# reduktor_net.net
KiCad netlist of a schematic drawn in EAGLE
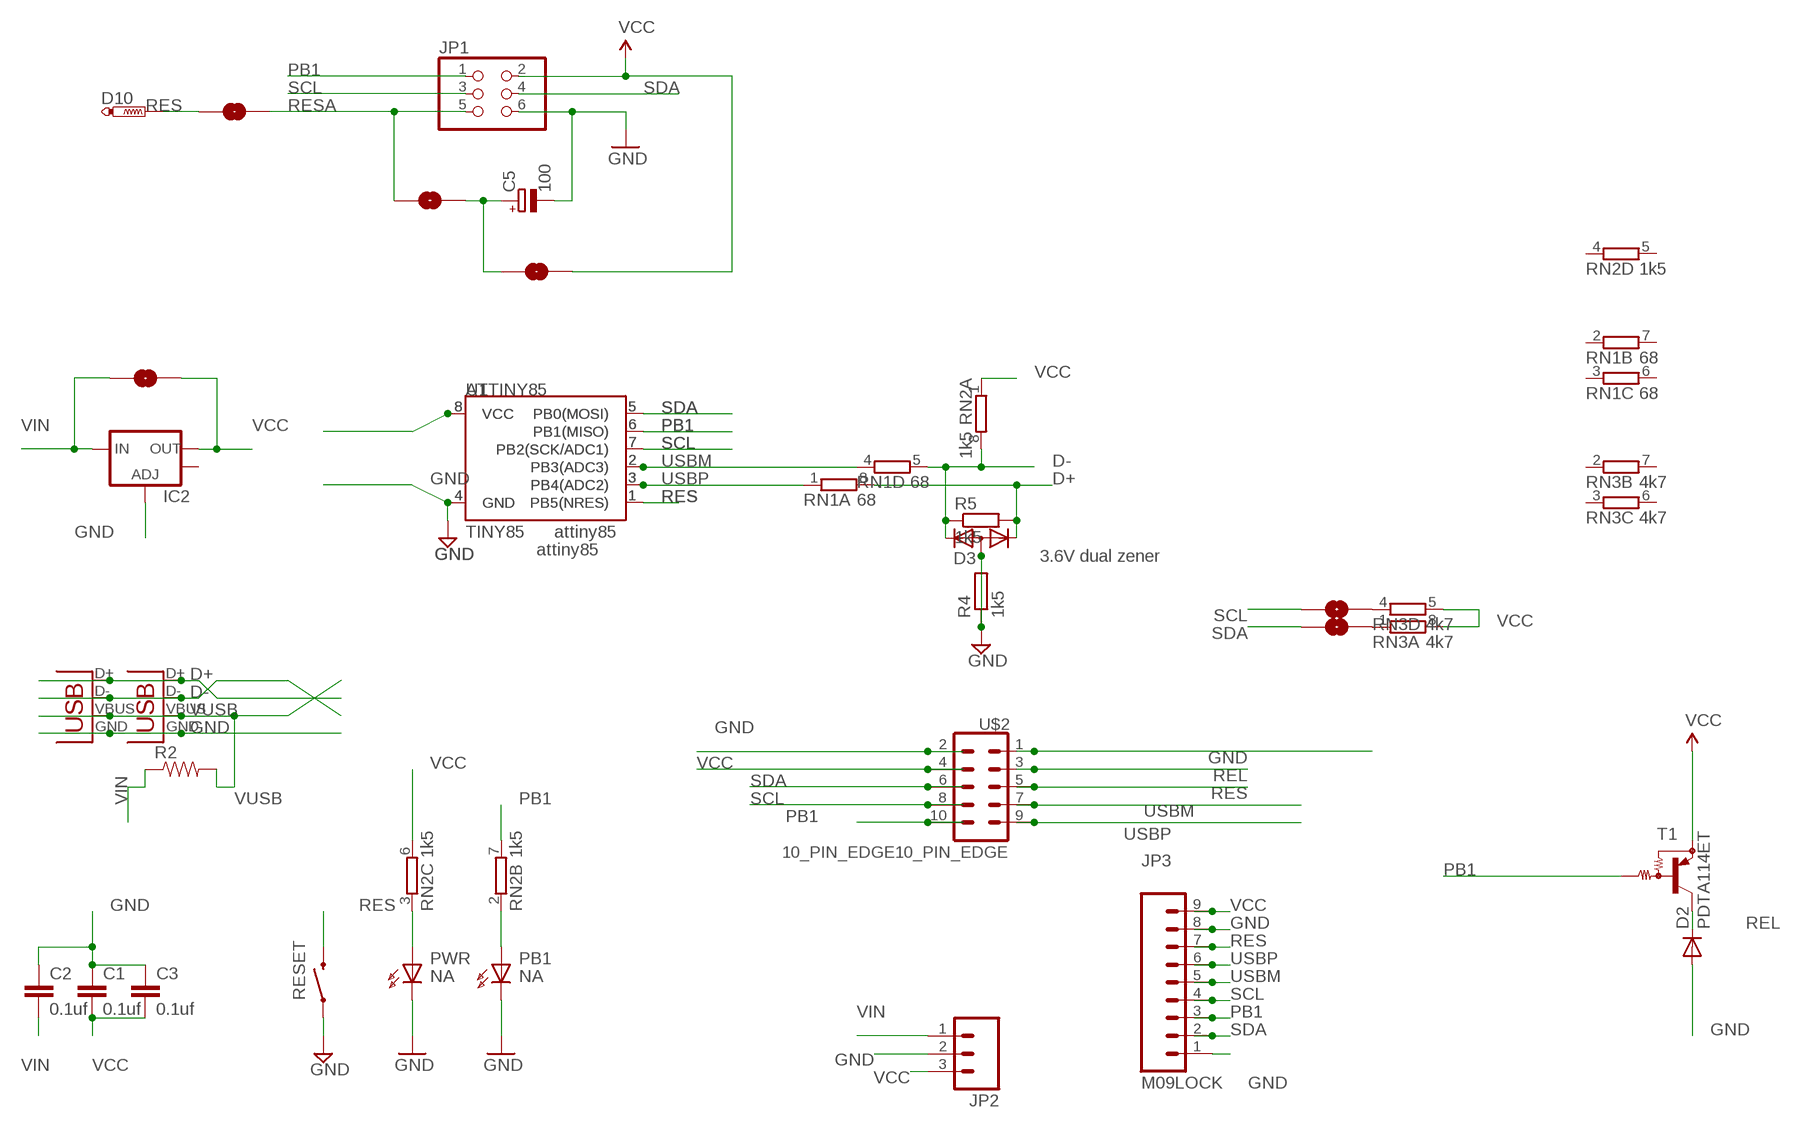
[diagram p0: schematic, sheet 1]

(export (version "E")
  (design (tool "Eeschema 10.0.6"))
  (components
    (comp (ref "ATTINY85")
      (value "ATTINY45")
      (footprint "eagle-import:SO08-EIAJ")
      (libsource (lib "eagle-import") (part "ATTINY45"))
    )
    (comp (ref "C1")
      (value "0.1uf")
      (footprint "eagle-import:0603-CAP")
      (libsource (lib "eagle-import") (part "CAP0603-CAP"))
    )
    (comp (ref "C2")
      (value "0.1uf")
      (footprint "eagle-import:0603-CAP")
      (libsource (lib "eagle-import") (part "CAP0603-CAP"))
    )
    (comp (ref "C3")
      (value "0.1uf")
      (footprint "eagle-import:0603-CAP")
      (libsource (lib "eagle-import") (part "CAP0603-CAP"))
    )
    (comp (ref "C5")
      (value "100")
      (footprint "eagle-import:153CLV-0405")
      (libsource (lib "eagle-import") (part "CPOL-EU153CLV-0405"))
    )
    (comp (ref "D2")
      (value "DIODESOD")
      (footprint "eagle-import:SOD-323")
      (libsource (lib "eagle-import") (part "DIODESOD"))
    )
    (comp (ref "D3")
      (value "3.6V dual zener")
      (footprint "eagle-import:SOT23")
      (libsource (lib "eagle-import") (part "DIODE-2CA|ACSOT23"))
    )
    (comp (ref "D10")
      (value "PTR1TP14SQ")
      (footprint "eagle-import:TP14SQ")
      (libsource (lib "eagle-import") (part "PTR1TP14SQ"))
    )
    (comp (ref "FUSE1")
      (value "SOLDERJUMPERNO")
      (footprint "eagle-import:SJ_2S-NO")
      (libsource (lib "eagle-import") (part "SOLDERJUMPERNO"))
    )
    (comp (ref "FUSE2")
      (value "SOLDERJUMPERNO")
      (footprint "eagle-import:SJ_2S-NO")
      (libsource (lib "eagle-import") (part "SOLDERJUMPERNO"))
    )
    (comp (ref "FUSE3")
      (value "SOLDERJUMPERNO")
      (footprint "eagle-import:SJ_2S-NO")
      (libsource (lib "eagle-import") (part "SOLDERJUMPERNO"))
    )
    (comp (ref "FUSE4")
      (value "SOLDERJUMPERNO")
      (footprint "eagle-import:SJ_2S-NO")
      (libsource (lib "eagle-import") (part "SOLDERJUMPERNO"))
    )
    (comp (ref "FUSE5")
      (value "SOLDERJUMPERNO")
      (footprint "eagle-import:SJ_2S-NO")
      (libsource (lib "eagle-import") (part "SOLDERJUMPERNO"))
    )
    (comp (ref "FUSE6")
      (value "SOLDERJUMPERNO")
      (footprint "eagle-import:SJ_2S-NO")
      (libsource (lib "eagle-import") (part "SOLDERJUMPERNO"))
    )
    (comp (ref "IC2")
      (value "V_REG_LM1117SOT223")
      (footprint "eagle-import:SOT223")
      (libsource (lib "eagle-import") (part "V_REG_LM1117SOT223"))
    )
    (comp (ref "JP1")
      (value "PINHD-2X3")
      (footprint "eagle-import:2X03")
      (libsource (lib "eagle-import") (part "PINHD-2X3"))
    )
    (comp (ref "JP2")
      (value "M03LOCK")
      (footprint "eagle-import:1X03_LOCK")
      (libsource (lib "eagle-import") (part "M03LOCK"))
    )
    (comp (ref "JP3")
      (value "M09LOCK")
      (footprint "eagle-import:1X09_LOCK")
      (libsource (lib "eagle-import") (part "M09LOCK"))
    )
    (comp (ref "PB1")
      (value "NA")
      (footprint "eagle-import:LED-0603")
      (libsource (lib "eagle-import") (part "LED0603DWS"))
    )
    (comp (ref "PWR")
      (value "NA")
      (footprint "eagle-import:LED-0603")
      (libsource (lib "eagle-import") (part "LED0603DWS"))
    )
    (comp (ref "R2")
      (value "RESISTOR0603-RES")
      (footprint "eagle-import:0603-RES")
      (libsource (lib "eagle-import") (part "RESISTOR0603-RES"))
    )
    (comp (ref "R4")
      (value "1k5")
      (footprint "eagle-import:R0603")
      (libsource (lib "eagle-import") (part "R-EU_R0603"))
    )
    (comp (ref "R5")
      (value "1k5")
      (footprint "eagle-import:R0603")
      (libsource (lib "eagle-import") (part "R-EU_R0603"))
    )
    (comp (ref "RESET")
      (value "SWITCH-MOMENTARY-2-SMD-1101NE")
      (footprint "eagle-import:TACTILE-SWITCH-1101NE")
      (libsource (lib "eagle-import") (part "SWITCH-MOMENTARY-2-SMD-1101NE"))
    )
    (comp (ref "RN1")
      (value "68")
      (footprint "eagle-import:0603-ARC")
      (libsource (lib "eagle-import") (part "4R-N0603-ARC"))
    )
    (comp (ref "RN2")
      (value "1k5")
      (footprint "eagle-import:0603-ARC")
      (libsource (lib "eagle-import") (part "4R-N0603-ARC"))
    )
    (comp (ref "RN3")
      (value "4k7")
      (footprint "eagle-import:0603-ARC")
      (fields (field (name "OC_FARNELL") "unknown") (field (name "OC_NEWARK") "unknown"))
      (libsource (lib "eagle-import") (part "4R-N0603-ARC"))
    )
    (comp (ref "T1")
      (value "PDTA114ET")
      (footprint "eagle-import:ES_SOT23-3")
      (libsource (lib "eagle-import") (part "ES_PNP-DRIVERSOT23-3"))
    )
    (comp (ref "U$2")
      (value "10_PIN_EDGE10_PIN_EDGE")
      (footprint "eagle-import:10_PIN_EDGE")
      (libsource (lib "eagle-import") (part "10_PIN_EDGE10_PIN_EDGE"))
    )
    (comp (ref "U1")
      (value "TINY85")
      (footprint "eagle-import:DIP08")
      (libsource (lib "eagle-import") (part "ATTINY45TINY45-20-DIP"))
    )
    (comp (ref "X5")
      (value "USBSMD")
      (footprint "eagle-import:USB-MINIB")
      (libsource (lib "eagle-import") (part "USBSMD"))
    )
    (comp (ref "X6")
      (value "USB-MICROB")
      (footprint "eagle-import:USB-MICROB")
      (libsource (lib "eagle-import") (part "USB-MICROB"))
    )
  )
  (nets
    (net (code "1") (name "/D+") (class "Default")
      (node (ref "D3") (pin "1") (pinfunction "K1_1") (pintype "passive"))
      (node (ref "R5") (pin "2") (pinfunction "2_2") (pintype "passive"))
      (node (ref "RN1") (pin "8") (pinfunction "2_8") (pintype "passive"))
      (node (ref "X5") (pin "D+") (pinfunction "D+_D+") (pintype "bidirectional"))
      (node (ref "X6") (pin "D+") (pinfunction "D+_D+") (pintype "bidirectional"))
    )
    (net (code "2") (name "/D-") (class "Default")
      (node (ref "D3") (pin "2") (pinfunction "K2_2") (pintype "passive"))
      (node (ref "R5") (pin "1") (pinfunction "1_1") (pintype "passive"))
      (node (ref "RN1") (pin "5") (pinfunction "2_5") (pintype "passive"))
      (node (ref "RN2") (pin "8") (pinfunction "2_8") (pintype "passive"))
      (node (ref "X5") (pin "D-") (pinfunction "D-_D-") (pintype "bidirectional"))
      (node (ref "X6") (pin "D-") (pinfunction "D-_D-") (pintype "bidirectional"))
    )
    (net (code "3") (name "/PB1") (class "Default")
      (node (ref "ATTINY85") (pin "6") (pinfunction "PB1(MISO)_6") (pintype "bidirectional"))
      (node (ref "JP1") (pin "1") (pinfunction "1_1") (pintype "passive"))
      (node (ref "JP3") (pin "3") (pinfunction "3_3") (pintype "passive"))
      (node (ref "RN2") (pin "7") (pinfunction "2_7") (pintype "passive"))
      (node (ref "T1") (pin "1") (pinfunction "B_1") (pintype "passive"))
      (node (ref "U$2") (pin "10") (pinfunction "10_10") (pintype "passive"))
      (node (ref "U1") (pin "6") (pinfunction "PB1(MISO)_6") (pintype "bidirectional"))
    )
    (net (code "4") (name "/REL") (class "Default")
      (node (ref "D2") (pin "1") (pinfunction "C_1") (pintype "passive"))
      (node (ref "T1") (pin "3") (pinfunction "C_3") (pintype "passive"))
      (node (ref "U$2") (pin "3") (pinfunction "3_3") (pintype "passive"))
    )
    (net (code "5") (name "/RES") (class "Default")
      (node (ref "ATTINY85") (pin "1") (pinfunction "PB5(NRES)_1") (pintype "bidirectional"))
      (node (ref "D10") (pin "TP") (pinfunction "TP_TP") (pintype "input"))
      (node (ref "FUSE1") (pin "1") (pinfunction "1_1") (pintype "passive"))
      (node (ref "JP3") (pin "7") (pinfunction "7_7") (pintype "passive"))
      (node (ref "RESET") (pin "P$2") (pinfunction "2_P$2") (pintype "passive"))
      (node (ref "U$2") (pin "5") (pinfunction "5_5") (pintype "passive"))
      (node (ref "U1") (pin "1") (pinfunction "PB5(NRES)_1") (pintype "bidirectional"))
    )
    (net (code "6") (name "/RESA") (class "Default")
      (node (ref "FUSE1") (pin "2") (pinfunction "2_2") (pintype "passive"))
      (node (ref "FUSE3") (pin "1") (pinfunction "1_1") (pintype "passive"))
      (node (ref "JP1") (pin "5") (pinfunction "5_5") (pintype "passive"))
    )
    (net (code "7") (name "/SCL") (class "Default")
      (node (ref "ATTINY85") (pin "7") (pinfunction "PB2(SCK/ADC1)_7") (pintype "bidirectional"))
      (node (ref "FUSE4") (pin "1") (pinfunction "1_1") (pintype "passive"))
      (node (ref "JP1") (pin "3") (pinfunction "3_3") (pintype "passive"))
      (node (ref "JP3") (pin "4") (pinfunction "4_4") (pintype "passive"))
      (node (ref "U$2") (pin "8") (pinfunction "8_8") (pintype "passive"))
      (node (ref "U1") (pin "7") (pinfunction "PB2(SCK/ADC1)_7") (pintype "bidirectional"))
    )
    (net (code "8") (name "/SDA") (class "Default")
      (node (ref "ATTINY85") (pin "5") (pinfunction "PB0(MOSI)_5") (pintype "bidirectional"))
      (node (ref "FUSE5") (pin "1") (pinfunction "1_1") (pintype "passive"))
      (node (ref "JP1") (pin "4") (pinfunction "4_4") (pintype "passive"))
      (node (ref "JP3") (pin "2") (pinfunction "2_2") (pintype "passive"))
      (node (ref "U$2") (pin "6") (pinfunction "6_6") (pintype "passive"))
      (node (ref "U1") (pin "5") (pinfunction "PB0(MOSI)_5") (pintype "bidirectional"))
    )
    (net (code "9") (name "/USBM") (class "Default")
      (node (ref "ATTINY85") (pin "2") (pinfunction "PB3(ADC3)_2") (pintype "bidirectional"))
      (node (ref "JP3") (pin "5") (pinfunction "5_5") (pintype "passive"))
      (node (ref "RN1") (pin "4") (pinfunction "1_4") (pintype "passive"))
      (node (ref "U$2") (pin "7") (pinfunction "7_7") (pintype "passive"))
      (node (ref "U1") (pin "2") (pinfunction "PB3(ADC3)_2") (pintype "bidirectional"))
    )
    (net (code "10") (name "/USBP") (class "Default")
      (node (ref "ATTINY85") (pin "3") (pinfunction "PB4(ADC2)_3") (pintype "bidirectional"))
      (node (ref "JP3") (pin "6") (pinfunction "6_6") (pintype "passive"))
      (node (ref "RN1") (pin "1") (pinfunction "1_1") (pintype "passive"))
      (node (ref "U$2") (pin "9") (pinfunction "9_9") (pintype "passive"))
      (node (ref "U1") (pin "3") (pinfunction "PB4(ADC2)_3") (pintype "bidirectional"))
    )
    (net (code "11") (name "/VIN") (class "Default")
      (node (ref "C2") (pin "2") (pinfunction "2_2") (pintype "passive"))
      (node (ref "FUSE2") (pin "1") (pinfunction "1_1") (pintype "passive"))
      (node (ref "IC2") (pin "3") (pinfunction "IN_3") (pintype "input"))
      (node (ref "JP2") (pin "1") (pinfunction "1_1") (pintype "passive"))
      (node (ref "R2") (pin "1") (pinfunction "1_1") (pintype "passive"))
    )
    (net (code "12") (name "/VUSB") (class "Default")
      (node (ref "R2") (pin "2") (pinfunction "2_2") (pintype "passive"))
      (node (ref "X5") (pin "VBUS") (pinfunction "VBUS_VBUS") (pintype "bidirectional"))
      (node (ref "X6") (pin "VBUS") (pinfunction "VBUS_VBUS") (pintype "bidirectional"))
    )
    (net (code "13") (name "GND") (class "Default")
      (node (ref "ATTINY85") (pin "4") (pinfunction "GND_4") (pintype "bidirectional"))
      (node (ref "C1") (pin "1") (pinfunction "1_1") (pintype "passive"))
      (node (ref "C2") (pin "1") (pinfunction "1_1") (pintype "passive"))
      (node (ref "C3") (pin "1") (pinfunction "1_1") (pintype "passive"))
      (node (ref "C5") (pin "-") (pinfunction "-_-") (pintype "passive"))
      (node (ref "D2") (pin "2") (pinfunction "A_2") (pintype "passive"))
      (node (ref "D3") (pin "3") (pinfunction "A_3") (pintype "passive"))
      (node (ref "IC2") (pin "1") (pinfunction "ADJ_1") (pintype "input"))
      (node (ref "JP1") (pin "6") (pinfunction "6_6") (pintype "passive"))
      (node (ref "JP2") (pin "2") (pinfunction "2_2") (pintype "passive"))
      (node (ref "JP3") (pin "1") (pinfunction "1_1") (pintype "passive"))
      (node (ref "JP3") (pin "8") (pinfunction "8_8") (pintype "passive"))
      (node (ref "PB1") (pin "C") (pinfunction "C_C") (pintype "passive"))
      (node (ref "PWR") (pin "C") (pinfunction "C_C") (pintype "passive"))
      (node (ref "R4") (pin "1") (pinfunction "1_1") (pintype "passive"))
      (node (ref "R4") (pin "2") (pinfunction "2_2") (pintype "passive"))
      (node (ref "RESET") (pin "P$1") (pinfunction "1_P$1") (pintype "passive"))
      (node (ref "U$2") (pin "1") (pinfunction "1_1") (pintype "passive"))
      (node (ref "U$2") (pin "2") (pinfunction "2_2") (pintype "passive"))
      (node (ref "U1") (pin "4") (pinfunction "GND_4") (pintype "bidirectional"))
      (node (ref "X5") (pin "GND") (pinfunction "GND_GND") (pintype "bidirectional"))
      (node (ref "X6") (pin "GND") (pinfunction "GND_GND") (pintype "bidirectional"))
    )
    (net (code "14") (name "Net-(C5-Pad+)") (class "Default")
      (node (ref "C5") (pin "+") (pinfunction "+_+") (pintype "passive"))
      (node (ref "FUSE3") (pin "2") (pinfunction "2_2") (pintype "passive"))
      (node (ref "FUSE6") (pin "2") (pinfunction "2_2") (pintype "passive"))
    )
    (net (code "15") (name "Net-(FUSE5-Pad2)") (class "Default")
      (node (ref "FUSE5") (pin "2") (pinfunction "2_2") (pintype "passive"))
      (node (ref "RN3") (pin "1") (pinfunction "1_1") (pintype "passive"))
    )
    (net (code "16") (name "Net-(RN2B-1)") (class "Default")
      (node (ref "PB1") (pin "A") (pinfunction "A_A") (pintype "passive"))
      (node (ref "RN2") (pin "2") (pinfunction "1_2") (pintype "passive"))
    )
    (net (code "17") (name "Net-(RN2C-1)") (class "Default")
      (node (ref "PWR") (pin "A") (pinfunction "A_A") (pintype "passive"))
      (node (ref "RN2") (pin "3") (pinfunction "1_3") (pintype "passive"))
    )
    (net (code "18") (name "Net-(RN3D-1)") (class "Default")
      (node (ref "FUSE4") (pin "2") (pinfunction "2_2") (pintype "passive"))
      (node (ref "RN3") (pin "4") (pinfunction "1_4") (pintype "passive"))
    )
    (net (code "19") (name "VCC") (class "Default")
      (node (ref "ATTINY85") (pin "8") (pinfunction "VCC_8") (pintype "bidirectional"))
      (node (ref "C1") (pin "2") (pinfunction "2_2") (pintype "passive"))
      (node (ref "C3") (pin "2") (pinfunction "2_2") (pintype "passive"))
      (node (ref "FUSE2") (pin "2") (pinfunction "2_2") (pintype "passive"))
      (node (ref "FUSE6") (pin "1") (pinfunction "1_1") (pintype "passive"))
      (node (ref "IC2") (pin "2") (pinfunction "OUT_2") (pintype "output"))
      (node (ref "JP1") (pin "2") (pinfunction "2_2") (pintype "passive"))
      (node (ref "JP2") (pin "3") (pinfunction "3_3") (pintype "passive"))
      (node (ref "JP3") (pin "9") (pinfunction "9_9") (pintype "passive"))
      (node (ref "RN2") (pin "1") (pinfunction "1_1") (pintype "passive"))
      (node (ref "RN2") (pin "6") (pinfunction "2_6") (pintype "passive"))
      (node (ref "RN3") (pin "5") (pinfunction "2_5") (pintype "passive"))
      (node (ref "RN3") (pin "8") (pinfunction "2_8") (pintype "passive"))
      (node (ref "T1") (pin "2") (pinfunction "E_2") (pintype "passive"))
      (node (ref "U$2") (pin "4") (pinfunction "4_4") (pintype "passive"))
      (node (ref "U1") (pin "8") (pinfunction "VCC_8") (pintype "bidirectional"))
    )
    (net (code "20") (name "unconnected-(IC2-OUT-Pad4)") (class "Default")
      (node (ref "IC2") (pin "4") (pinfunction "OUT_4") (pintype "output"))
    )
    (net (code "21") (name "unconnected-(RN1B-1-Pad2)") (class "Default")
      (node (ref "RN1") (pin "2") (pinfunction "1_2") (pintype "passive"))
    )
    (net (code "22") (name "unconnected-(RN1B-2-Pad7)") (class "Default")
      (node (ref "RN1") (pin "7") (pinfunction "2_7") (pintype "passive"))
    )
    (net (code "23") (name "unconnected-(RN1C-1-Pad3)") (class "Default")
      (node (ref "RN1") (pin "3") (pinfunction "1_3") (pintype "passive"))
    )
    (net (code "24") (name "unconnected-(RN1C-2-Pad6)") (class "Default")
      (node (ref "RN1") (pin "6") (pinfunction "2_6") (pintype "passive"))
    )
    (net (code "25") (name "unconnected-(RN2D-1-Pad4)") (class "Default")
      (node (ref "RN2") (pin "4") (pinfunction "1_4") (pintype "passive"))
    )
    (net (code "26") (name "unconnected-(RN2D-2-Pad5)") (class "Default")
      (node (ref "RN2") (pin "5") (pinfunction "2_5") (pintype "passive"))
    )
    (net (code "27") (name "unconnected-(RN3B-1-Pad2)") (class "Default")
      (node (ref "RN3") (pin "2") (pinfunction "1_2") (pintype "passive"))
    )
    (net (code "28") (name "unconnected-(RN3B-2-Pad7)") (class "Default")
      (node (ref "RN3") (pin "7") (pinfunction "2_7") (pintype "passive"))
    )
    (net (code "29") (name "unconnected-(RN3C-1-Pad3)") (class "Default")
      (node (ref "RN3") (pin "3") (pinfunction "1_3") (pintype "passive"))
    )
    (net (code "30") (name "unconnected-(RN3C-2-Pad6)") (class "Default")
      (node (ref "RN3") (pin "6") (pinfunction "2_6") (pintype "passive"))
    )
  )
)
